# SCH3_Fan_Control.net
KiCad netlist of a schematic drawn in Altium Designer
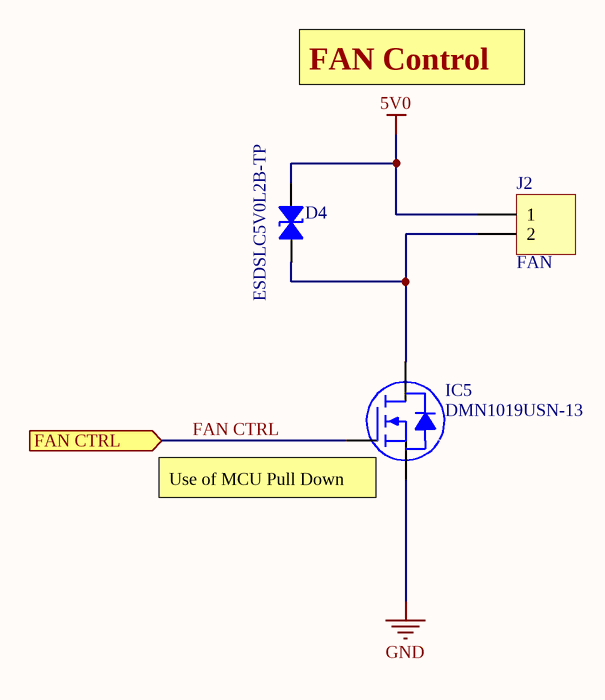
[diagram p0: SCH3_Fan_Control.SchDoc]

(export (version "E")
  (design (tool "Eeschema 10.0.6"))
  (components
    (comp (ref "D4")
      (value "ESDSLC5V0L2B-TP")
      (footprint "0402")
      (description "5.5V, ESD PROTECTION DEVICES, DF")
      (fields (field (name "MANUFACTURER") "Micro Commercial Co"))
      (libsource (lib "Celestial Altium Library - altium_library") (part "Diode TVS"))
    )
    (comp (ref "IC5")
      (value "DMN1019USN-13")
      (footprint "DIODES SOT-23-3")
      (description "MOSFET N-CH 12V 9.3A SC59")
      (fields (field (name "MANUFACTURER") "Diodes Incorporated"))
      (libsource (lib "Celestial Altium Library - altium_library") (part "DIODES INC MOSFET N-CH SOT-23-3"))
    )
    (comp (ref "J2")
      (value "FAN")
      (footprint "FAN Connections")
      (description "Fan Connection Test Points")
      (fields (field (name "PUBLISHER") "Altium Limited"))
      (libsource (lib "SCH_Lib") (part "FAN Connection"))
    )
  )
  (nets
    (net (code "1") (name "/FAN CTRL") (class "Default")
      (node (ref "IC5") (pin "1") (pinfunction "G_1") (pintype "passive"))
    )
    (net (code "2") (name "5V0") (class "Default")
      (node (ref "D4") (pin "2") (pinfunction "2_2") (pintype "passive"))
      (node (ref "J2") (pin "1") (pinfunction "1_1") (pintype "passive"))
    )
    (net (code "3") (name "GND") (class "Default")
      (node (ref "IC5") (pin "2") (pinfunction "S_2") (pintype "passive"))
    )
    (net (code "4") (name "Net-(IC5-D)") (class "Default")
      (node (ref "D4") (pin "1") (pinfunction "1_1") (pintype "passive"))
      (node (ref "IC5") (pin "3") (pinfunction "D_3") (pintype "passive"))
      (node (ref "J2") (pin "2") (pinfunction "2_2") (pintype "passive"))
    )
  )
)
